# uMote-pic.net
KiCad netlist of a schematic drawn in Altium Designer
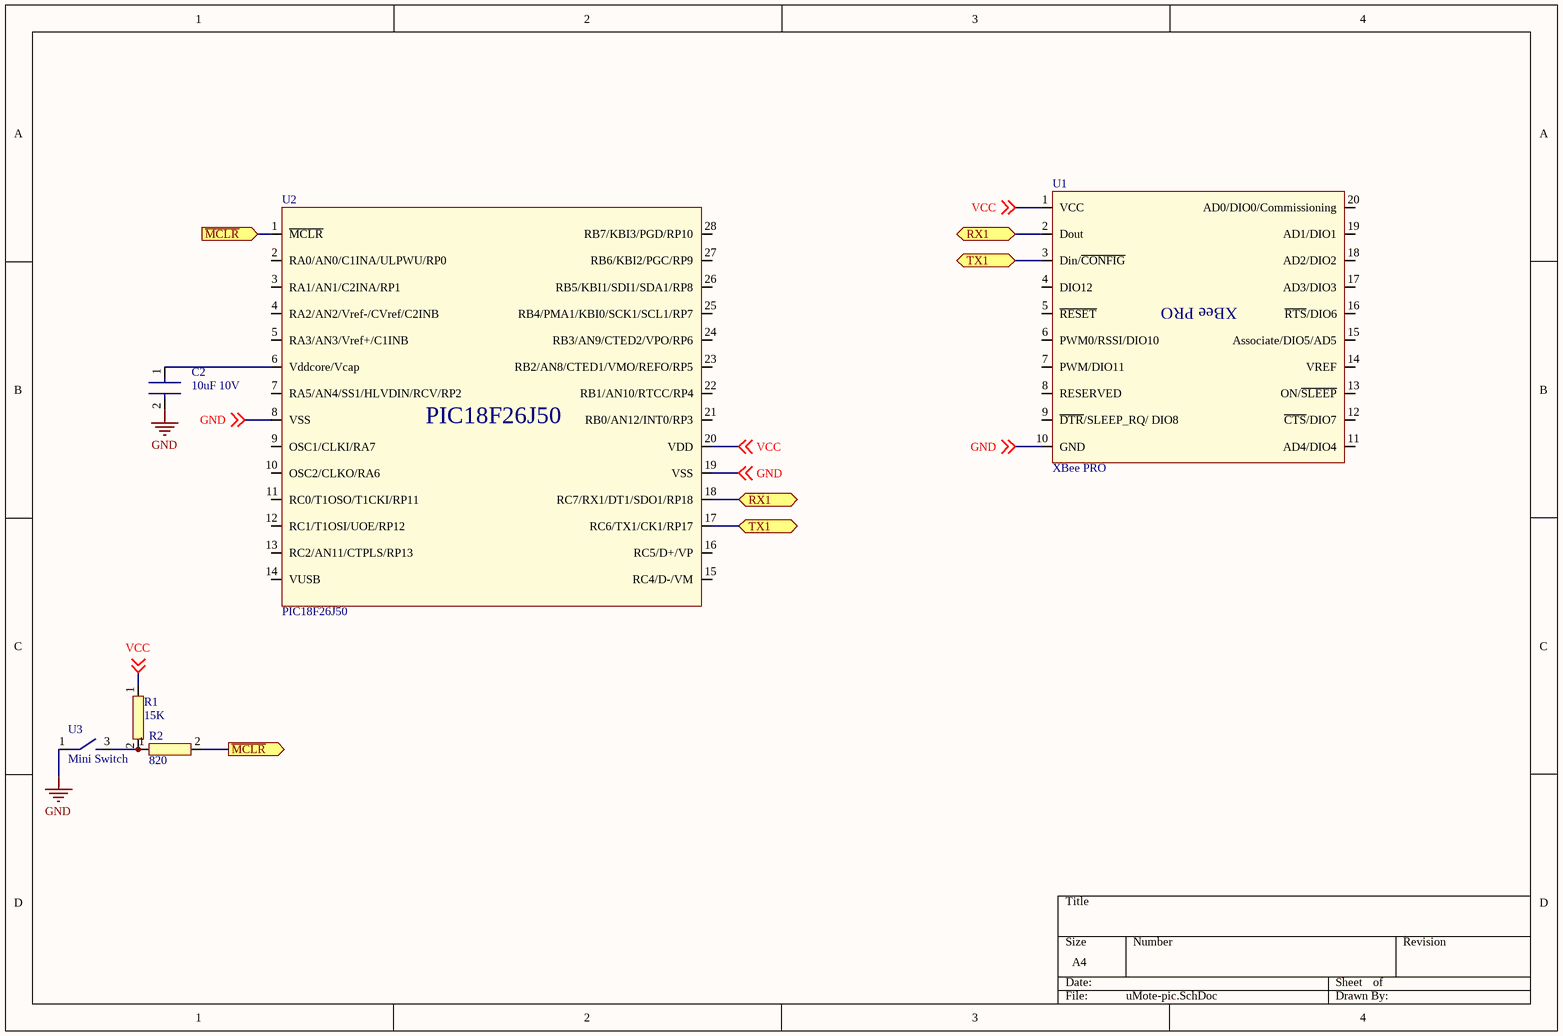
[diagram p0: uMote-pic.SchDoc]

(export (version "E")
  (design (tool "Eeschema 10.0.6"))
  (components
    (comp (ref "C2")
      (value "10uF 10V")
      (footprint "Capacitor EIA 1206")
      (libsource (lib "uMote") (part "TDK C3216X7R1C106K"))
    )
    (comp (ref "R1") (value "15K") (footprint "EIA 1206") (libsource (lib "") (part "RES 1206_1")))
    (comp (ref "R2") (value "820") (footprint "EIA 1206") (libsource (lib "uMote") (part "RES 1206")))
    (comp (ref "U1") (value "XBee PRO") (libsource (lib "uMote") (part "XBee PRO")))
    (comp (ref "U2") (value "PIC18F26J50") (libsource (lib "uMote") (part "PIC18F26J50")))
    (comp (ref "U3")
      (value "Mini Switch")
      (footprint "Mini Switch")
      (libsource (lib "uMote") (part "Mini Switch"))
    )
  )
  (nets
    (net (code "1") (name "/MCLR") (class "Default")
      (node (ref "R2") (pin "2") (pinfunction "2_2") (pintype "passive"))
      (node (ref "U2") (pin "1") (pinfunction "MCLR_1") (pintype "input"))
    )
    (net (code "2") (name "/RX1") (class "Default")
      (node (ref "U1") (pin "2") (pinfunction "Dout_2") (pintype "passive"))
      (node (ref "U2") (pin "18") (pinfunction "RC7/RX1/DT1/SDO1/RP18_18") (pintype "passive"))
    )
    (net (code "3") (name "/TX1") (class "Default")
      (node (ref "U1") (pin "3") (pinfunction "Din/~{CONFIG}_3") (pintype "passive"))
      (node (ref "U2") (pin "17") (pinfunction "RC6/TX1/CK1/RP17_17") (pintype "passive"))
    )
    (net (code "4") (name "GND") (class "Default")
      (node (ref "C2") (pin "2") (pinfunction "2_2") (pintype "passive"))
      (node (ref "U1") (pin "10") (pinfunction "GND_10") (pintype "passive"))
      (node (ref "U2") (pin "19") (pinfunction "VSS_19") (pintype "passive"))
      (node (ref "U2") (pin "8") (pinfunction "VSS_8") (pintype "passive"))
      (node (ref "U3") (pin "1") (pinfunction "1_1") (pintype "passive"))
    )
    (net (code "5") (name "Net-(R1-Pad2)") (class "Default")
      (node (ref "R1") (pin "2") (pinfunction "2_2") (pintype "passive"))
      (node (ref "R2") (pin "1") (pinfunction "1_1") (pintype "passive"))
      (node (ref "U3") (pin "3") (pinfunction "3_3") (pintype "passive"))
    )
    (net (code "6") (name "Net-(U2-Vddcore{slash}Vcap)") (class "Default")
      (node (ref "C2") (pin "1") (pinfunction "1_1") (pintype "passive"))
      (node (ref "U2") (pin "6") (pinfunction "Vddcore/Vcap_6") (pintype "passive"))
    )
    (net (code "7") (name "VCC") (class "Default")
      (node (ref "R1") (pin "1") (pinfunction "1_1") (pintype "passive"))
      (node (ref "U1") (pin "1") (pinfunction "VCC_1") (pintype "passive"))
      (node (ref "U2") (pin "20") (pinfunction "VDD_20") (pintype "passive"))
    )
    (net (code "8") (name "unconnected-(U1-AD0{slash}DIO0{slash}Commissioning-Pad20)") (class "Default")
      (node (ref "U1") (pin "20") (pinfunction "AD0/DIO0/Commissioning_20") (pintype "power_in"))
    )
    (net (code "9") (name "unconnected-(U1-AD1{slash}DIO1-Pad19)") (class "Default")
      (node (ref "U1") (pin "19") (pinfunction "AD1/DIO1_19") (pintype "passive"))
    )
    (net (code "10") (name "unconnected-(U1-AD2{slash}DIO2-Pad18)") (class "Default")
      (node (ref "U1") (pin "18") (pinfunction "AD2/DIO2_18") (pintype "passive"))
    )
    (net (code "11") (name "unconnected-(U1-AD3{slash}DIO3-Pad17)") (class "Default")
      (node (ref "U1") (pin "17") (pinfunction "AD3/DIO3_17") (pintype "passive"))
    )
    (net (code "12") (name "unconnected-(U1-AD4{slash}DIO4-Pad11)") (class "Default")
      (node (ref "U1") (pin "11") (pinfunction "AD4/DIO4_11") (pintype "passive"))
    )
    (net (code "13") (name "unconnected-(U1-Associate{slash}DIO5{slash}AD5-Pad15)") (class "Default")
      (node (ref "U1") (pin "15") (pinfunction "Associate/DIO5/AD5_15") (pintype "passive"))
    )
    (net (code "14") (name "unconnected-(U1-DIO12-Pad4)") (class "Default")
      (node (ref "U1") (pin "4") (pinfunction "DIO12_4") (pintype "passive"))
    )
    (net (code "15") (name "unconnected-(U1-ON{slash}~{SLEEP}-Pad13)") (class "Default")
      (node (ref "U1") (pin "13") (pinfunction "ON/~{SLEEP}_13") (pintype "passive"))
    )
    (net (code "16") (name "unconnected-(U1-PWM0{slash}RSSI{slash}DIO10-Pad6)") (class "Default")
      (node (ref "U1") (pin "6") (pinfunction "PWM0/RSSI/DIO10_6") (pintype "passive"))
    )
    (net (code "17") (name "unconnected-(U1-PWM{slash}DIO11-Pad7)") (class "Default")
      (node (ref "U1") (pin "7") (pinfunction "PWM/DIO11_7") (pintype "passive"))
    )
    (net (code "18") (name "unconnected-(U1-RESERVED-Pad8)") (class "Default")
      (node (ref "U1") (pin "8") (pinfunction "RESERVED_8") (pintype "passive"))
    )
    (net (code "19") (name "unconnected-(U1-RESET-Pad5)") (class "Default")
      (node (ref "U1") (pin "5") (pinfunction "RESET_5") (pintype "passive"))
    )
    (net (code "20") (name "unconnected-(U1-VREF-Pad14)") (class "Default")
      (node (ref "U1") (pin "14") (pinfunction "VREF_14") (pintype "passive"))
    )
    (net (code "21") (name "unconnected-(U1-~{CTS}{slash}DIO7-Pad12)") (class "Default")
      (node (ref "U1") (pin "12") (pinfunction "~{CTS}/DIO7_12") (pintype "passive"))
    )
    (net (code "22") (name "unconnected-(U1-~{DTR}{slash}SLEEP_RQ{slash}_DIO8-Pad9)") (class "Default")
      (node (ref "U1") (pin "9") (pinfunction "~{DTR}/SLEEP_RQ/_DIO8_9") (pintype "passive"))
    )
    (net (code "23") (name "unconnected-(U1-~{RTS}{slash}DIO6-Pad16)") (class "Default")
      (node (ref "U1") (pin "16") (pinfunction "~{RTS}/DIO6_16") (pintype "passive"))
    )
    (net (code "24") (name "unconnected-(U2-OSC1{slash}CLKI{slash}RA7-Pad9)") (class "Default")
      (node (ref "U2") (pin "9") (pinfunction "OSC1/CLKI/RA7_9") (pintype "passive"))
    )
    (net (code "25") (name "unconnected-(U2-OSC2{slash}CLKO{slash}RA6-Pad10)") (class "Default")
      (node (ref "U2") (pin "10") (pinfunction "OSC2/CLKO/RA6_10") (pintype "passive"))
    )
    (net (code "26") (name "unconnected-(U2-RA0{slash}AN0{slash}C1INA{slash}ULPWU{slash}RP0-Pad2)") (class "Default")
      (node (ref "U2") (pin "2") (pinfunction "RA0/AN0/C1INA/ULPWU/RP0_2") (pintype "passive"))
    )
    (net (code "27") (name "unconnected-(U2-RA1{slash}AN1{slash}C2INA{slash}RP1-Pad3)") (class "Default")
      (node (ref "U2") (pin "3") (pinfunction "RA1/AN1/C2INA/RP1_3") (pintype "passive"))
    )
    (net (code "28") (name "unconnected-(U2-RA2{slash}AN2{slash}Vref-{slash}CVref{slash}C2INB-Pad4)") (class "Default")
      (node (ref "U2") (pin "4") (pinfunction "RA2/AN2/Vref-/CVref/C2INB_4") (pintype "passive"))
    )
    (net (code "29") (name "unconnected-(U2-RA3{slash}AN3{slash}Vref+{slash}C1INB-Pad5)") (class "Default")
      (node (ref "U2") (pin "5") (pinfunction "RA3/AN3/Vref+/C1INB_5") (pintype "passive"))
    )
    (net (code "30") (name "unconnected-(U2-RA5{slash}AN4{slash}SS1{slash}HLVDIN{slash}RCV{slash}RP2-Pad7)") (class "Default")
      (node (ref "U2") (pin "7") (pinfunction "RA5/AN4/SS1/HLVDIN/RCV/RP2_7") (pintype "passive"))
    )
    (net (code "31") (name "unconnected-(U2-RB0{slash}AN12{slash}INT0{slash}RP3-Pad21)") (class "Default")
      (node (ref "U2") (pin "21") (pinfunction "RB0/AN12/INT0/RP3_21") (pintype "passive"))
    )
    (net (code "32") (name "unconnected-(U2-RB1{slash}AN10{slash}RTCC{slash}RP4-Pad22)") (class "Default")
      (node (ref "U2") (pin "22") (pinfunction "RB1/AN10/RTCC/RP4_22") (pintype "passive"))
    )
    (net (code "33") (name "unconnected-(U2-RB2{slash}AN8{slash}CTED1{slash}VMO{slash}REFO{slash}RP5-Pad23)") (class "Default")
      (node (ref "U2") (pin "23") (pinfunction "RB2/AN8/CTED1/VMO/REFO/RP5_23") (pintype "passive"))
    )
    (net (code "34") (name "unconnected-(U2-RB3{slash}AN9{slash}CTED2{slash}VPO{slash}RP6-Pad24)") (class "Default")
      (node (ref "U2") (pin "24") (pinfunction "RB3/AN9/CTED2/VPO/RP6_24") (pintype "passive"))
    )
    (net (code "35") (name "unconnected-(U2-RB4{slash}PMA1{slash}KBI0{slash}SCK1{slash}SCL1{slash}RP7-Pad25)") (class "Default")
      (node (ref "U2") (pin "25") (pinfunction "RB4/PMA1/KBI0/SCK1/SCL1/RP7_25") (pintype "passive"))
    )
    (net (code "36") (name "unconnected-(U2-RB5{slash}KBI1{slash}SDI1{slash}SDA1{slash}RP8-Pad26)") (class "Default")
      (node (ref "U2") (pin "26") (pinfunction "RB5/KBI1/SDI1/SDA1/RP8_26") (pintype "passive"))
    )
    (net (code "37") (name "unconnected-(U2-RB6{slash}KBI2{slash}PGC{slash}RP9-Pad27)") (class "Default")
      (node (ref "U2") (pin "27") (pinfunction "RB6/KBI2/PGC/RP9_27") (pintype "passive"))
    )
    (net (code "38") (name "unconnected-(U2-RB7{slash}KBI3{slash}PGD{slash}RP10-Pad28)") (class "Default")
      (node (ref "U2") (pin "28") (pinfunction "RB7/KBI3/PGD/RP10_28") (pintype "passive"))
    )
    (net (code "39") (name "unconnected-(U2-RC0{slash}T1OSO{slash}T1CKI{slash}RP11-Pad11)") (class "Default")
      (node (ref "U2") (pin "11") (pinfunction "RC0/T1OSO/T1CKI/RP11_11") (pintype "passive"))
    )
    (net (code "40") (name "unconnected-(U2-RC1{slash}T1OSI{slash}UOE{slash}RP12-Pad12)") (class "Default")
      (node (ref "U2") (pin "12") (pinfunction "RC1/T1OSI/UOE/RP12_12") (pintype "passive"))
    )
    (net (code "41") (name "unconnected-(U2-RC2{slash}AN11{slash}CTPLS{slash}RP13-Pad13)") (class "Default")
      (node (ref "U2") (pin "13") (pinfunction "RC2/AN11/CTPLS/RP13_13") (pintype "passive"))
    )
    (net (code "42") (name "unconnected-(U2-RC4{slash}D-{slash}VM-Pad15)") (class "Default")
      (node (ref "U2") (pin "15") (pinfunction "RC4/D-/VM_15") (pintype "passive"))
    )
    (net (code "43") (name "unconnected-(U2-RC5{slash}D+{slash}VP-Pad16)") (class "Default")
      (node (ref "U2") (pin "16") (pinfunction "RC5/D+/VP_16") (pintype "passive"))
    )
    (net (code "44") (name "unconnected-(U2-VUSB-Pad14)") (class "Default")
      (node (ref "U2") (pin "14") (pinfunction "VUSB_14") (pintype "passive"))
    )
  )
)
